# 02_CPU_Connect.net
KiCad netlist of a schematic drawn in Altium Designer
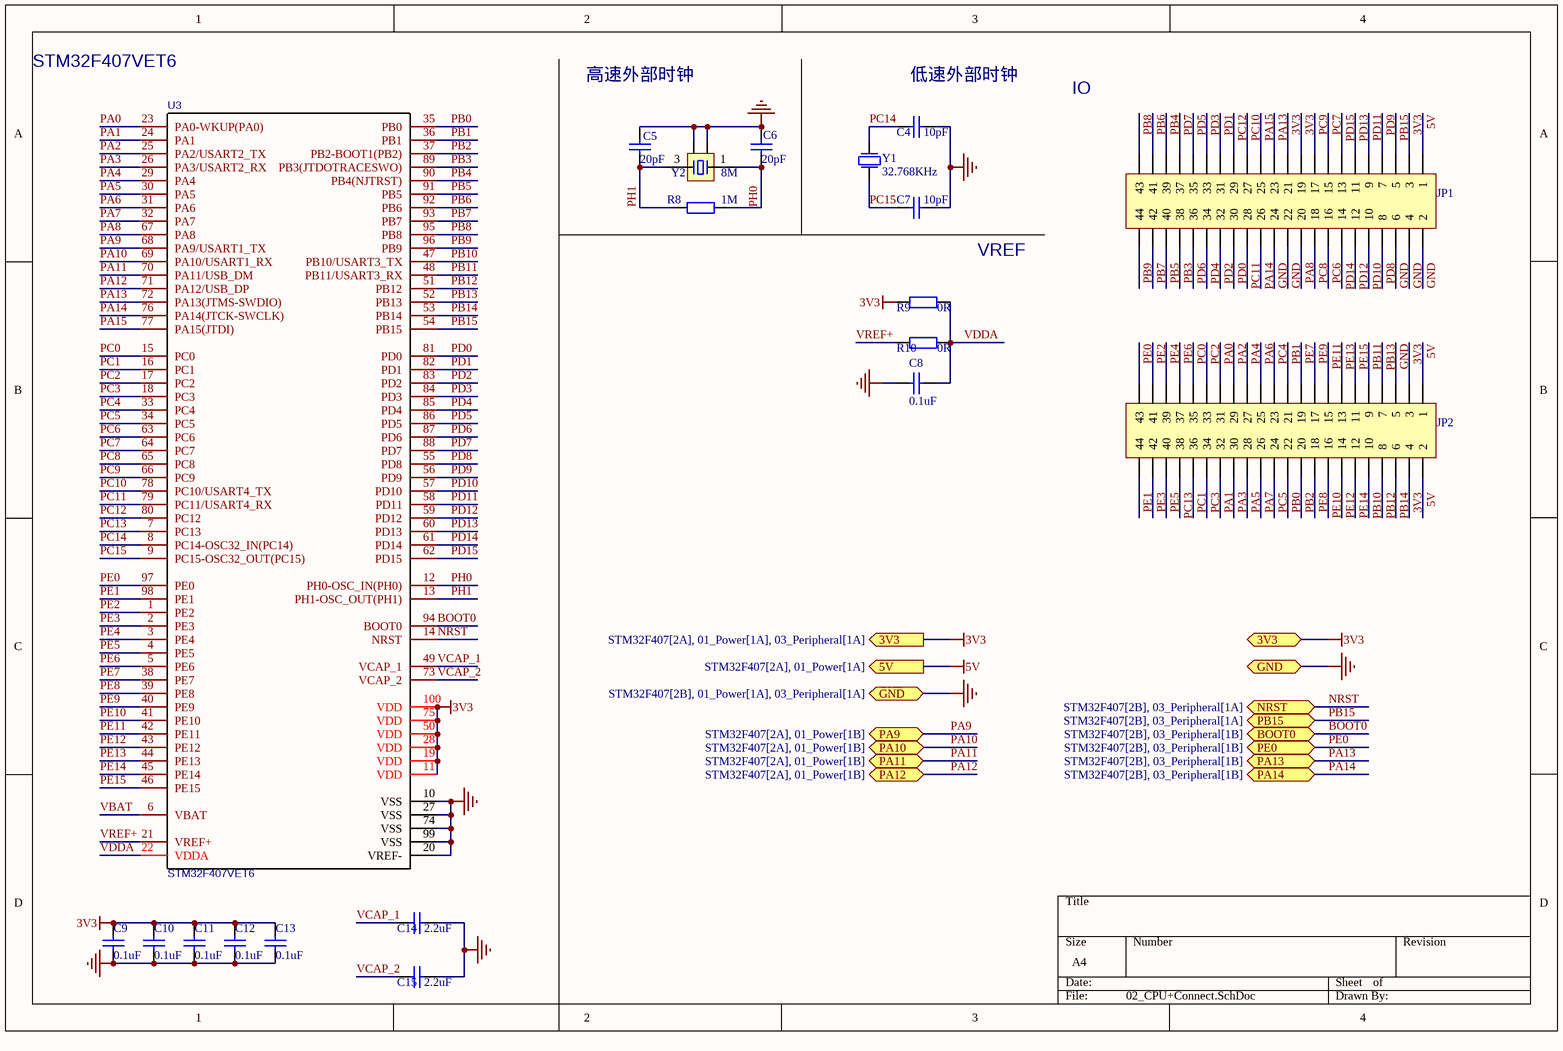
[diagram p0: 02_CPU+Connect.SchDoc]

(export (version "E")
  (design (tool "Eeschema 10.0.6"))
  (components
    (comp (ref "C4") (value "10pF") (footprint "C 0402_L") (libsource (lib "Schlib1") (part "Cap")))
    (comp (ref "C5") (value "20pF") (footprint "C 0402_L") (libsource (lib "Schlib1") (part "Cap")))
    (comp (ref "C6") (value "20pF") (footprint "C 0402_L") (libsource (lib "Schlib1") (part "Cap")))
    (comp (ref "C7") (value "10pF") (footprint "C 0402_L") (libsource (lib "Schlib1") (part "Cap")))
    (comp (ref "C8") (value "0.1uF") (footprint "C 0402_L") (libsource (lib "Schlib1") (part "Cap")))
    (comp (ref "C9") (value "0.1uF") (footprint "C 0402_L") (libsource (lib "Schlib1") (part "Cap")))
    (comp (ref "C10") (value "0.1uF") (footprint "C 0402_L") (libsource (lib "Schlib1") (part "Cap")))
    (comp (ref "C11") (value "0.1uF") (footprint "C 0402_L") (libsource (lib "Schlib1") (part "Cap")))
    (comp (ref "C12") (value "0.1uF") (footprint "C 0402_L") (libsource (lib "Schlib1") (part "Cap")))
    (comp (ref "C13") (value "0.1uF") (footprint "C 0402_L") (libsource (lib "Schlib1") (part "Cap")))
    (comp (ref "C14") (value "2.2uF") (footprint "C 0402_L") (libsource (lib "Schlib1") (part "Cap")))
    (comp (ref "C15") (value "2.2uF") (footprint "C 0402_L") (libsource (lib "Schlib1") (part "Cap")))
    (comp (ref "JP1")
      (value "Header 2x22")
      (footprint "HDR2.54-LI-2x22P")
      (description "2x22P接插件")
      (libsource (lib "Schlib1") (part "Header 2x22"))
    )
    (comp (ref "JP2")
      (value "Header 2x22")
      (footprint "HDR2.54-LI-2x22P")
      (description "2x22P接插件")
      (libsource (lib "Schlib1") (part "Header 2x22"))
    )
    (comp (ref "R8") (value "1M") (footprint "R 0402_L") (libsource (lib "Schlib1") (part "Res")))
    (comp (ref "R9") (value "0R") (footprint "R 0402_L") (libsource (lib "Schlib1") (part "Res")))
    (comp (ref "R10") (value "0R") (footprint "R 0402_L") (libsource (lib "Schlib1") (part "Res")))
    (comp (ref "U3")
      (value "STM32F407VET6")
      (footprint "LQFP100 14x14_N")
      (fields (field (name "BOM_SUPPLIER PART") "C28730") (field (name "SUBPART_NO") "1"))
      (libsource (lib "Schlib1") (part "STM32F407VET6"))
    )
    (comp (ref "Y1")
      (value "32.768KHz")
      (footprint "FC135-3.2X1.5")
      (libsource (lib "Schlib1") (part "XTAL-2P"))
    )
    (comp (ref "Y2")
      (value "8M")
      (footprint "OSC 3225-4P")
      (description "4脚无源晶振")
      (libsource (lib "Schlib1") (part "XTAL-4P"))
    )
  )
  (nets
    (net (code "1") (name "/BOOT0") (class "Default")
      (node (ref "U3") (pin "94") (pinfunction "BOOT0_94") (pintype "passive"))
    )
    (net (code "2") (name "/NRST") (class "Default")
      (node (ref "U3") (pin "14") (pinfunction "NRST_14") (pintype "passive"))
    )
    (net (code "3") (name "/PA0") (class "Default")
      (node (ref "JP2") (pin "31") (pinfunction "31_31") (pintype "passive"))
      (node (ref "U3") (pin "23") (pinfunction "PA0-WKUP(PA0)_23") (pintype "passive"))
    )
    (net (code "4") (name "/PA1") (class "Default")
      (node (ref "JP2") (pin "32") (pinfunction "32_32") (pintype "passive"))
      (node (ref "U3") (pin "24") (pinfunction "PA1_24") (pintype "passive"))
    )
    (net (code "5") (name "/PA2") (class "Default")
      (node (ref "JP2") (pin "29") (pinfunction "29_29") (pintype "passive"))
      (node (ref "U3") (pin "25") (pinfunction "PA2/USART2_TX_25") (pintype "passive"))
    )
    (net (code "6") (name "/PA3") (class "Default")
      (node (ref "JP2") (pin "30") (pinfunction "30_30") (pintype "passive"))
      (node (ref "U3") (pin "26") (pinfunction "PA3/USART2_RX_26") (pintype "passive"))
    )
    (net (code "7") (name "/PA4") (class "Default")
      (node (ref "JP2") (pin "27") (pinfunction "27_27") (pintype "passive"))
      (node (ref "U3") (pin "29") (pinfunction "PA4_29") (pintype "passive"))
    )
    (net (code "8") (name "/PA5") (class "Default")
      (node (ref "JP2") (pin "28") (pinfunction "28_28") (pintype "passive"))
      (node (ref "U3") (pin "30") (pinfunction "PA5_30") (pintype "passive"))
    )
    (net (code "9") (name "/PA6") (class "Default")
      (node (ref "JP2") (pin "25") (pinfunction "25_25") (pintype "passive"))
      (node (ref "U3") (pin "31") (pinfunction "PA6_31") (pintype "passive"))
    )
    (net (code "10") (name "/PA7") (class "Default")
      (node (ref "JP2") (pin "26") (pinfunction "26_26") (pintype "passive"))
      (node (ref "U3") (pin "32") (pinfunction "PA7_32") (pintype "passive"))
    )
    (net (code "11") (name "/PA8") (class "Default")
      (node (ref "JP1") (pin "20") (pinfunction "20_20") (pintype "passive"))
      (node (ref "U3") (pin "67") (pinfunction "PA8_67") (pintype "passive"))
    )
    (net (code "12") (name "/PA9") (class "Default")
      (node (ref "U3") (pin "68") (pinfunction "PA9/USART1_TX_68") (pintype "passive"))
    )
    (net (code "13") (name "/PA10") (class "Default")
      (node (ref "U3") (pin "69") (pinfunction "PA10/USART1_RX_69") (pintype "passive"))
    )
    (net (code "14") (name "/PA11") (class "Default")
      (node (ref "U3") (pin "70") (pinfunction "PA11/USB_DM_70") (pintype "passive"))
    )
    (net (code "15") (name "/PA12") (class "Default")
      (node (ref "U3") (pin "71") (pinfunction "PA12/USB_DP_71") (pintype "passive"))
    )
    (net (code "16") (name "/PA13") (class "Default")
      (node (ref "JP1") (pin "23") (pinfunction "23_23") (pintype "passive"))
      (node (ref "U3") (pin "72") (pinfunction "PA13(JTMS-SWDIO)_72") (pintype "passive"))
    )
    (net (code "17") (name "/PA14") (class "Default")
      (node (ref "JP1") (pin "26") (pinfunction "26_26") (pintype "passive"))
      (node (ref "U3") (pin "76") (pinfunction "PA14(JTCK-SWCLK)_76") (pintype "passive"))
    )
    (net (code "18") (name "/PA15") (class "Default")
      (node (ref "JP1") (pin "25") (pinfunction "25_25") (pintype "passive"))
      (node (ref "U3") (pin "77") (pinfunction "PA15(JTDI)_77") (pintype "passive"))
    )
    (net (code "19") (name "/PB0") (class "Default")
      (node (ref "JP2") (pin "22") (pinfunction "22_22") (pintype "passive"))
      (node (ref "U3") (pin "35") (pinfunction "PB0_35") (pintype "passive"))
    )
    (net (code "20") (name "/PB1") (class "Default")
      (node (ref "JP2") (pin "21") (pinfunction "21_21") (pintype "passive"))
      (node (ref "U3") (pin "36") (pinfunction "PB1_36") (pintype "passive"))
    )
    (net (code "21") (name "/PB2") (class "Default")
      (node (ref "JP2") (pin "20") (pinfunction "20_20") (pintype "passive"))
      (node (ref "U3") (pin "37") (pinfunction "PB2-BOOT1(PB2)_37") (pintype "passive"))
    )
    (net (code "22") (name "/PB3") (class "Default")
      (node (ref "JP1") (pin "38") (pinfunction "38_38") (pintype "passive"))
      (node (ref "U3") (pin "89") (pinfunction "PB3(JTDOTRACESWO)_89") (pintype "passive"))
    )
    (net (code "23") (name "/PB4") (class "Default")
      (node (ref "JP1") (pin "39") (pinfunction "39_39") (pintype "passive"))
      (node (ref "U3") (pin "90") (pinfunction "PB4(NJTRST)_90") (pintype "passive"))
    )
    (net (code "24") (name "/PB5") (class "Default")
      (node (ref "JP1") (pin "40") (pinfunction "40_40") (pintype "passive"))
      (node (ref "U3") (pin "91") (pinfunction "PB5_91") (pintype "passive"))
    )
    (net (code "25") (name "/PB6") (class "Default")
      (node (ref "JP1") (pin "41") (pinfunction "41_41") (pintype "passive"))
      (node (ref "U3") (pin "92") (pinfunction "PB6_92") (pintype "passive"))
    )
    (net (code "26") (name "/PB7") (class "Default")
      (node (ref "JP1") (pin "42") (pinfunction "42_42") (pintype "passive"))
      (node (ref "U3") (pin "93") (pinfunction "PB7_93") (pintype "passive"))
    )
    (net (code "27") (name "/PB8") (class "Default")
      (node (ref "JP1") (pin "43") (pinfunction "43_43") (pintype "passive"))
      (node (ref "U3") (pin "95") (pinfunction "PB8_95") (pintype "passive"))
    )
    (net (code "28") (name "/PB9") (class "Default")
      (node (ref "JP1") (pin "44") (pinfunction "44_44") (pintype "passive"))
      (node (ref "U3") (pin "96") (pinfunction "PB9_96") (pintype "passive"))
    )
    (net (code "29") (name "/PB10") (class "Default")
      (node (ref "JP2") (pin "10") (pinfunction "10_10") (pintype "passive"))
      (node (ref "U3") (pin "47") (pinfunction "PB10/USART3_TX_47") (pintype "passive"))
    )
    (net (code "30") (name "/PB11") (class "Default")
      (node (ref "JP2") (pin "9") (pinfunction "9_9") (pintype "passive"))
      (node (ref "U3") (pin "48") (pinfunction "PB11/USART3_RX_48") (pintype "passive"))
    )
    (net (code "31") (name "/PB12") (class "Default")
      (node (ref "JP2") (pin "8") (pinfunction "8_8") (pintype "passive"))
      (node (ref "U3") (pin "51") (pinfunction "PB12_51") (pintype "passive"))
    )
    (net (code "32") (name "/PB13") (class "Default")
      (node (ref "JP2") (pin "7") (pinfunction "7_7") (pintype "passive"))
      (node (ref "U3") (pin "52") (pinfunction "PB13_52") (pintype "passive"))
    )
    (net (code "33") (name "/PB14") (class "Default")
      (node (ref "JP2") (pin "6") (pinfunction "6_6") (pintype "passive"))
      (node (ref "U3") (pin "53") (pinfunction "PB14_53") (pintype "passive"))
    )
    (net (code "34") (name "/PB15") (class "Default")
      (node (ref "JP1") (pin "5") (pinfunction "5_5") (pintype "passive"))
      (node (ref "U3") (pin "54") (pinfunction "PB15_54") (pintype "passive"))
    )
    (net (code "35") (name "/PC0") (class "Default")
      (node (ref "JP2") (pin "35") (pinfunction "35_35") (pintype "passive"))
      (node (ref "U3") (pin "15") (pinfunction "PC0_15") (pintype "passive"))
    )
    (net (code "36") (name "/PC1") (class "Default")
      (node (ref "JP2") (pin "36") (pinfunction "36_36") (pintype "passive"))
      (node (ref "U3") (pin "16") (pinfunction "PC1_16") (pintype "passive"))
    )
    (net (code "37") (name "/PC2") (class "Default")
      (node (ref "JP2") (pin "33") (pinfunction "33_33") (pintype "passive"))
      (node (ref "U3") (pin "17") (pinfunction "PC2_17") (pintype "passive"))
    )
    (net (code "38") (name "/PC3") (class "Default")
      (node (ref "JP2") (pin "34") (pinfunction "34_34") (pintype "passive"))
      (node (ref "U3") (pin "18") (pinfunction "PC3_18") (pintype "passive"))
    )
    (net (code "39") (name "/PC4") (class "Default")
      (node (ref "JP2") (pin "23") (pinfunction "23_23") (pintype "passive"))
      (node (ref "U3") (pin "33") (pinfunction "PC4_33") (pintype "passive"))
    )
    (net (code "40") (name "/PC5") (class "Default")
      (node (ref "JP2") (pin "24") (pinfunction "24_24") (pintype "passive"))
      (node (ref "U3") (pin "34") (pinfunction "PC5_34") (pintype "passive"))
    )
    (net (code "41") (name "/PC6") (class "Default")
      (node (ref "JP1") (pin "16") (pinfunction "16_16") (pintype "passive"))
      (node (ref "U3") (pin "63") (pinfunction "PC6_63") (pintype "passive"))
    )
    (net (code "42") (name "/PC7") (class "Default")
      (node (ref "JP1") (pin "15") (pinfunction "15_15") (pintype "passive"))
      (node (ref "U3") (pin "64") (pinfunction "PC7_64") (pintype "passive"))
    )
    (net (code "43") (name "/PC8") (class "Default")
      (node (ref "JP1") (pin "18") (pinfunction "18_18") (pintype "passive"))
      (node (ref "U3") (pin "65") (pinfunction "PC8_65") (pintype "passive"))
    )
    (net (code "44") (name "/PC9") (class "Default")
      (node (ref "JP1") (pin "17") (pinfunction "17_17") (pintype "passive"))
      (node (ref "U3") (pin "66") (pinfunction "PC9_66") (pintype "passive"))
    )
    (net (code "45") (name "/PC10") (class "Default")
      (node (ref "JP1") (pin "27") (pinfunction "27_27") (pintype "passive"))
      (node (ref "U3") (pin "78") (pinfunction "PC10/USART4_TX_78") (pintype "passive"))
    )
    (net (code "46") (name "/PC11") (class "Default")
      (node (ref "JP1") (pin "28") (pinfunction "28_28") (pintype "passive"))
      (node (ref "U3") (pin "79") (pinfunction "PC11/USART4_RX_79") (pintype "passive"))
    )
    (net (code "47") (name "/PC12") (class "Default")
      (node (ref "JP1") (pin "29") (pinfunction "29_29") (pintype "passive"))
      (node (ref "U3") (pin "80") (pinfunction "PC12_80") (pintype "passive"))
    )
    (net (code "48") (name "/PC13") (class "Default")
      (node (ref "JP2") (pin "38") (pinfunction "38_38") (pintype "passive"))
      (node (ref "U3") (pin "7") (pinfunction "PC13_7") (pintype "passive"))
    )
    (net (code "49") (name "/PC14") (class "Default")
      (node (ref "C4") (pin "2") (pinfunction "2_2") (pintype "passive"))
      (node (ref "U3") (pin "8") (pinfunction "PC14-OSC32_IN(PC14)_8") (pintype "passive"))
      (node (ref "Y1") (pin "1") (pinfunction "P1_1") (pintype "passive"))
    )
    (net (code "50") (name "/PC15") (class "Default")
      (node (ref "C7") (pin "2") (pinfunction "2_2") (pintype "passive"))
      (node (ref "U3") (pin "9") (pinfunction "PC15-OSC32_OUT(PC15)_9") (pintype "passive"))
      (node (ref "Y1") (pin "2") (pinfunction "P2_2") (pintype "passive"))
    )
    (net (code "51") (name "/PD0") (class "Default")
      (node (ref "JP1") (pin "30") (pinfunction "30_30") (pintype "passive"))
      (node (ref "U3") (pin "81") (pinfunction "PD0_81") (pintype "passive"))
    )
    (net (code "52") (name "/PD1") (class "Default")
      (node (ref "JP1") (pin "31") (pinfunction "31_31") (pintype "passive"))
      (node (ref "U3") (pin "82") (pinfunction "PD1_82") (pintype "passive"))
    )
    (net (code "53") (name "/PD2") (class "Default")
      (node (ref "JP1") (pin "32") (pinfunction "32_32") (pintype "passive"))
      (node (ref "U3") (pin "83") (pinfunction "PD2_83") (pintype "passive"))
    )
    (net (code "54") (name "/PD3") (class "Default")
      (node (ref "JP1") (pin "33") (pinfunction "33_33") (pintype "passive"))
      (node (ref "U3") (pin "84") (pinfunction "PD3_84") (pintype "passive"))
    )
    (net (code "55") (name "/PD4") (class "Default")
      (node (ref "JP1") (pin "34") (pinfunction "34_34") (pintype "passive"))
      (node (ref "U3") (pin "85") (pinfunction "PD4_85") (pintype "passive"))
    )
    (net (code "56") (name "/PD5") (class "Default")
      (node (ref "JP1") (pin "35") (pinfunction "35_35") (pintype "passive"))
      (node (ref "U3") (pin "86") (pinfunction "PD5_86") (pintype "passive"))
    )
    (net (code "57") (name "/PD6") (class "Default")
      (node (ref "JP1") (pin "36") (pinfunction "36_36") (pintype "passive"))
      (node (ref "U3") (pin "87") (pinfunction "PD6_87") (pintype "passive"))
    )
    (net (code "58") (name "/PD7") (class "Default")
      (node (ref "JP1") (pin "37") (pinfunction "37_37") (pintype "passive"))
      (node (ref "U3") (pin "88") (pinfunction "PD7_88") (pintype "passive"))
    )
    (net (code "59") (name "/PD8") (class "Default")
      (node (ref "JP1") (pin "8") (pinfunction "8_8") (pintype "passive"))
      (node (ref "U3") (pin "55") (pinfunction "PD8_55") (pintype "passive"))
    )
    (net (code "60") (name "/PD9") (class "Default")
      (node (ref "JP1") (pin "7") (pinfunction "7_7") (pintype "passive"))
      (node (ref "U3") (pin "56") (pinfunction "PD9_56") (pintype "passive"))
    )
    (net (code "61") (name "/PD10") (class "Default")
      (node (ref "JP1") (pin "10") (pinfunction "10_10") (pintype "passive"))
      (node (ref "U3") (pin "57") (pinfunction "PD10_57") (pintype "passive"))
    )
    (net (code "62") (name "/PD11") (class "Default")
      (node (ref "JP1") (pin "9") (pinfunction "9_9") (pintype "passive"))
      (node (ref "U3") (pin "58") (pinfunction "PD11_58") (pintype "passive"))
    )
    (net (code "63") (name "/PD12") (class "Default")
      (node (ref "JP1") (pin "12") (pinfunction "12_12") (pintype "passive"))
      (node (ref "U3") (pin "59") (pinfunction "PD12_59") (pintype "passive"))
    )
    (net (code "64") (name "/PD13") (class "Default")
      (node (ref "JP1") (pin "11") (pinfunction "11_11") (pintype "passive"))
      (node (ref "U3") (pin "60") (pinfunction "PD13_60") (pintype "passive"))
    )
    (net (code "65") (name "/PD14") (class "Default")
      (node (ref "JP1") (pin "14") (pinfunction "14_14") (pintype "passive"))
      (node (ref "U3") (pin "61") (pinfunction "PD14_61") (pintype "passive"))
    )
    (net (code "66") (name "/PD15") (class "Default")
      (node (ref "JP1") (pin "13") (pinfunction "13_13") (pintype "passive"))
      (node (ref "U3") (pin "62") (pinfunction "PD15_62") (pintype "passive"))
    )
    (net (code "67") (name "/PE0") (class "Default")
      (node (ref "JP2") (pin "43") (pinfunction "43_43") (pintype "passive"))
      (node (ref "U3") (pin "97") (pinfunction "PE0_97") (pintype "passive"))
    )
    (net (code "68") (name "/PE1") (class "Default")
      (node (ref "JP2") (pin "44") (pinfunction "44_44") (pintype "passive"))
      (node (ref "U3") (pin "98") (pinfunction "PE1_98") (pintype "passive"))
    )
    (net (code "69") (name "/PE2") (class "Default")
      (node (ref "JP2") (pin "41") (pinfunction "41_41") (pintype "passive"))
      (node (ref "U3") (pin "1") (pinfunction "PE2_1") (pintype "passive"))
    )
    (net (code "70") (name "/PE3") (class "Default")
      (node (ref "JP2") (pin "42") (pinfunction "42_42") (pintype "passive"))
      (node (ref "U3") (pin "2") (pinfunction "PE3_2") (pintype "passive"))
    )
    (net (code "71") (name "/PE4") (class "Default")
      (node (ref "JP2") (pin "39") (pinfunction "39_39") (pintype "passive"))
      (node (ref "U3") (pin "3") (pinfunction "PE4_3") (pintype "passive"))
    )
    (net (code "72") (name "/PE5") (class "Default")
      (node (ref "JP2") (pin "40") (pinfunction "40_40") (pintype "passive"))
      (node (ref "U3") (pin "4") (pinfunction "PE5_4") (pintype "passive"))
    )
    (net (code "73") (name "/PE6") (class "Default")
      (node (ref "JP2") (pin "37") (pinfunction "37_37") (pintype "passive"))
      (node (ref "U3") (pin "5") (pinfunction "PE6_5") (pintype "passive"))
    )
    (net (code "74") (name "/PE7") (class "Default")
      (node (ref "JP2") (pin "19") (pinfunction "19_19") (pintype "passive"))
      (node (ref "U3") (pin "38") (pinfunction "PE7_38") (pintype "passive"))
    )
    (net (code "75") (name "/PE8") (class "Default")
      (node (ref "JP2") (pin "18") (pinfunction "18_18") (pintype "passive"))
      (node (ref "U3") (pin "39") (pinfunction "PE8_39") (pintype "passive"))
    )
    (net (code "76") (name "/PE9") (class "Default")
      (node (ref "JP2") (pin "17") (pinfunction "17_17") (pintype "passive"))
      (node (ref "U3") (pin "40") (pinfunction "PE9_40") (pintype "passive"))
    )
    (net (code "77") (name "/PE10") (class "Default")
      (node (ref "JP2") (pin "16") (pinfunction "16_16") (pintype "passive"))
      (node (ref "U3") (pin "41") (pinfunction "PE10_41") (pintype "passive"))
    )
    (net (code "78") (name "/PE11") (class "Default")
      (node (ref "JP2") (pin "15") (pinfunction "15_15") (pintype "passive"))
      (node (ref "U3") (pin "42") (pinfunction "PE11_42") (pintype "passive"))
    )
    (net (code "79") (name "/PE12") (class "Default")
      (node (ref "JP2") (pin "14") (pinfunction "14_14") (pintype "passive"))
      (node (ref "U3") (pin "43") (pinfunction "PE12_43") (pintype "passive"))
    )
    (net (code "80") (name "/PE13") (class "Default")
      (node (ref "JP2") (pin "13") (pinfunction "13_13") (pintype "passive"))
      (node (ref "U3") (pin "44") (pinfunction "PE13_44") (pintype "passive"))
    )
    (net (code "81") (name "/PE14") (class "Default")
      (node (ref "JP2") (pin "12") (pinfunction "12_12") (pintype "passive"))
      (node (ref "U3") (pin "45") (pinfunction "PE14_45") (pintype "passive"))
    )
    (net (code "82") (name "/PE15") (class "Default")
      (node (ref "JP2") (pin "11") (pinfunction "11_11") (pintype "passive"))
      (node (ref "U3") (pin "46") (pinfunction "PE15_46") (pintype "passive"))
    )
    (net (code "83") (name "/PH0") (class "Default")
      (node (ref "C6") (pin "2") (pinfunction "2_2") (pintype "passive"))
      (node (ref "R8") (pin "1") (pinfunction "1_1") (pintype "passive"))
      (node (ref "U3") (pin "12") (pinfunction "PH0-OSC_IN(PH0)_12") (pintype "passive"))
      (node (ref "Y2") (pin "1") (pinfunction "1_1") (pintype "passive"))
    )
    (net (code "84") (name "/PH1") (class "Default")
      (node (ref "C5") (pin "2") (pinfunction "2_2") (pintype "passive"))
      (node (ref "R8") (pin "2") (pinfunction "2_2") (pintype "passive"))
      (node (ref "U3") (pin "13") (pinfunction "PH1-OSC_OUT(PH1)_13") (pintype "passive"))
      (node (ref "Y2") (pin "3") (pinfunction "3_3") (pintype "passive"))
    )
    (net (code "85") (name "/VBAT") (class "Default")
      (node (ref "U3") (pin "6") (pinfunction "VBAT_6") (pintype "passive"))
    )
    (net (code "86") (name "/VCAP_1") (class "Default")
      (node (ref "C14") (pin "2") (pinfunction "2_2") (pintype "passive"))
      (node (ref "U3") (pin "49") (pinfunction "VCAP_1_49") (pintype "passive"))
    )
    (net (code "87") (name "/VCAP_2") (class "Default")
      (node (ref "C15") (pin "2") (pinfunction "2_2") (pintype "passive"))
      (node (ref "U3") (pin "73") (pinfunction "VCAP_2_73") (pintype "passive"))
    )
    (net (code "88") (name "/VDDA") (class "Default")
      (node (ref "C8") (pin "2") (pinfunction "2_2") (pintype "passive"))
      (node (ref "R10") (pin "1") (pinfunction "1_1") (pintype "passive"))
      (node (ref "R9") (pin "1") (pinfunction "1_1") (pintype "passive"))
      (node (ref "U3") (pin "22") (pinfunction "VDDA_22") (pintype "passive"))
    )
    (net (code "89") (name "/VREF+") (class "Default")
      (node (ref "R10") (pin "2") (pinfunction "2_2") (pintype "passive"))
      (node (ref "U3") (pin "21") (pinfunction "VREF+_21") (pintype "passive"))
    )
    (net (code "90") (name "3V3") (class "Default")
      (node (ref "C10") (pin "1") (pinfunction "1_1") (pintype "passive"))
      (node (ref "C11") (pin "1") (pinfunction "1_1") (pintype "passive"))
      (node (ref "C12") (pin "1") (pinfunction "1_1") (pintype "passive"))
      (node (ref "C13") (pin "1") (pinfunction "1_1") (pintype "passive"))
      (node (ref "C9") (pin "1") (pinfunction "1_1") (pintype "passive"))
      (node (ref "JP1") (pin "19") (pinfunction "19_19") (pintype "passive"))
      (node (ref "JP1") (pin "21") (pinfunction "21_21") (pintype "passive"))
      (node (ref "JP1") (pin "3") (pinfunction "3_3") (pintype "passive"))
      (node (ref "JP2") (pin "3") (pinfunction "3_3") (pintype "passive"))
      (node (ref "JP2") (pin "4") (pinfunction "4_4") (pintype "passive"))
      (node (ref "R9") (pin "2") (pinfunction "2_2") (pintype "passive"))
      (node (ref "U3") (pin "100") (pinfunction "VDD_100") (pintype "passive"))
      (node (ref "U3") (pin "11") (pinfunction "VDD_11") (pintype "passive"))
      (node (ref "U3") (pin "19") (pinfunction "VDD_19") (pintype "passive"))
      (node (ref "U3") (pin "28") (pinfunction "VDD_28") (pintype "passive"))
      (node (ref "U3") (pin "50") (pinfunction "VDD_50") (pintype "passive"))
      (node (ref "U3") (pin "75") (pinfunction "VDD_75") (pintype "passive"))
    )
    (net (code "91") (name "5V") (class "Default")
      (node (ref "JP1") (pin "1") (pinfunction "1_1") (pintype "passive"))
      (node (ref "JP2") (pin "1") (pinfunction "1_1") (pintype "passive"))
      (node (ref "JP2") (pin "2") (pinfunction "2_2") (pintype "passive"))
    )
    (net (code "92") (name "GND") (class "Default")
      (node (ref "C10") (pin "2") (pinfunction "2_2") (pintype "passive"))
      (node (ref "C11") (pin "2") (pinfunction "2_2") (pintype "passive"))
      (node (ref "C12") (pin "2") (pinfunction "2_2") (pintype "passive"))
      (node (ref "C13") (pin "2") (pinfunction "2_2") (pintype "passive"))
      (node (ref "C14") (pin "1") (pinfunction "1_1") (pintype "passive"))
      (node (ref "C15") (pin "1") (pinfunction "1_1") (pintype "passive"))
      (node (ref "C4") (pin "1") (pinfunction "1_1") (pintype "passive"))
      (node (ref "C5") (pin "1") (pinfunction "1_1") (pintype "passive"))
      (node (ref "C6") (pin "1") (pinfunction "1_1") (pintype "passive"))
      (node (ref "C7") (pin "1") (pinfunction "1_1") (pintype "passive"))
      (node (ref "C8") (pin "1") (pinfunction "1_1") (pintype "passive"))
      (node (ref "C9") (pin "2") (pinfunction "2_2") (pintype "passive"))
      (node (ref "JP1") (pin "2") (pinfunction "2_2") (pintype "passive"))
      (node (ref "JP1") (pin "22") (pinfunction "22_22") (pintype "passive"))
      (node (ref "JP1") (pin "24") (pinfunction "24_24") (pintype "passive"))
      (node (ref "JP1") (pin "4") (pinfunction "4_4") (pintype "passive"))
      (node (ref "JP1") (pin "6") (pinfunction "6_6") (pintype "passive"))
      (node (ref "JP2") (pin "5") (pinfunction "5_5") (pintype "passive"))
      (node (ref "U3") (pin "10") (pinfunction "VSS_10") (pintype "passive"))
      (node (ref "U3") (pin "20") (pinfunction "VREF-_20") (pintype "passive"))
      (node (ref "U3") (pin "27") (pinfunction "VSS_27") (pintype "passive"))
      (node (ref "U3") (pin "74") (pinfunction "VSS_74") (pintype "passive"))
      (node (ref "U3") (pin "99") (pinfunction "VSS_99") (pintype "passive"))
      (node (ref "Y2") (pin "2") (pinfunction "2_2") (pintype "passive"))
      (node (ref "Y2") (pin "4") (pinfunction "4_4") (pintype "passive"))
    )
  )
)
